# stm32103c8t6-10x10-v2.net
KiCad netlist of a schematic drawn in EAGLE
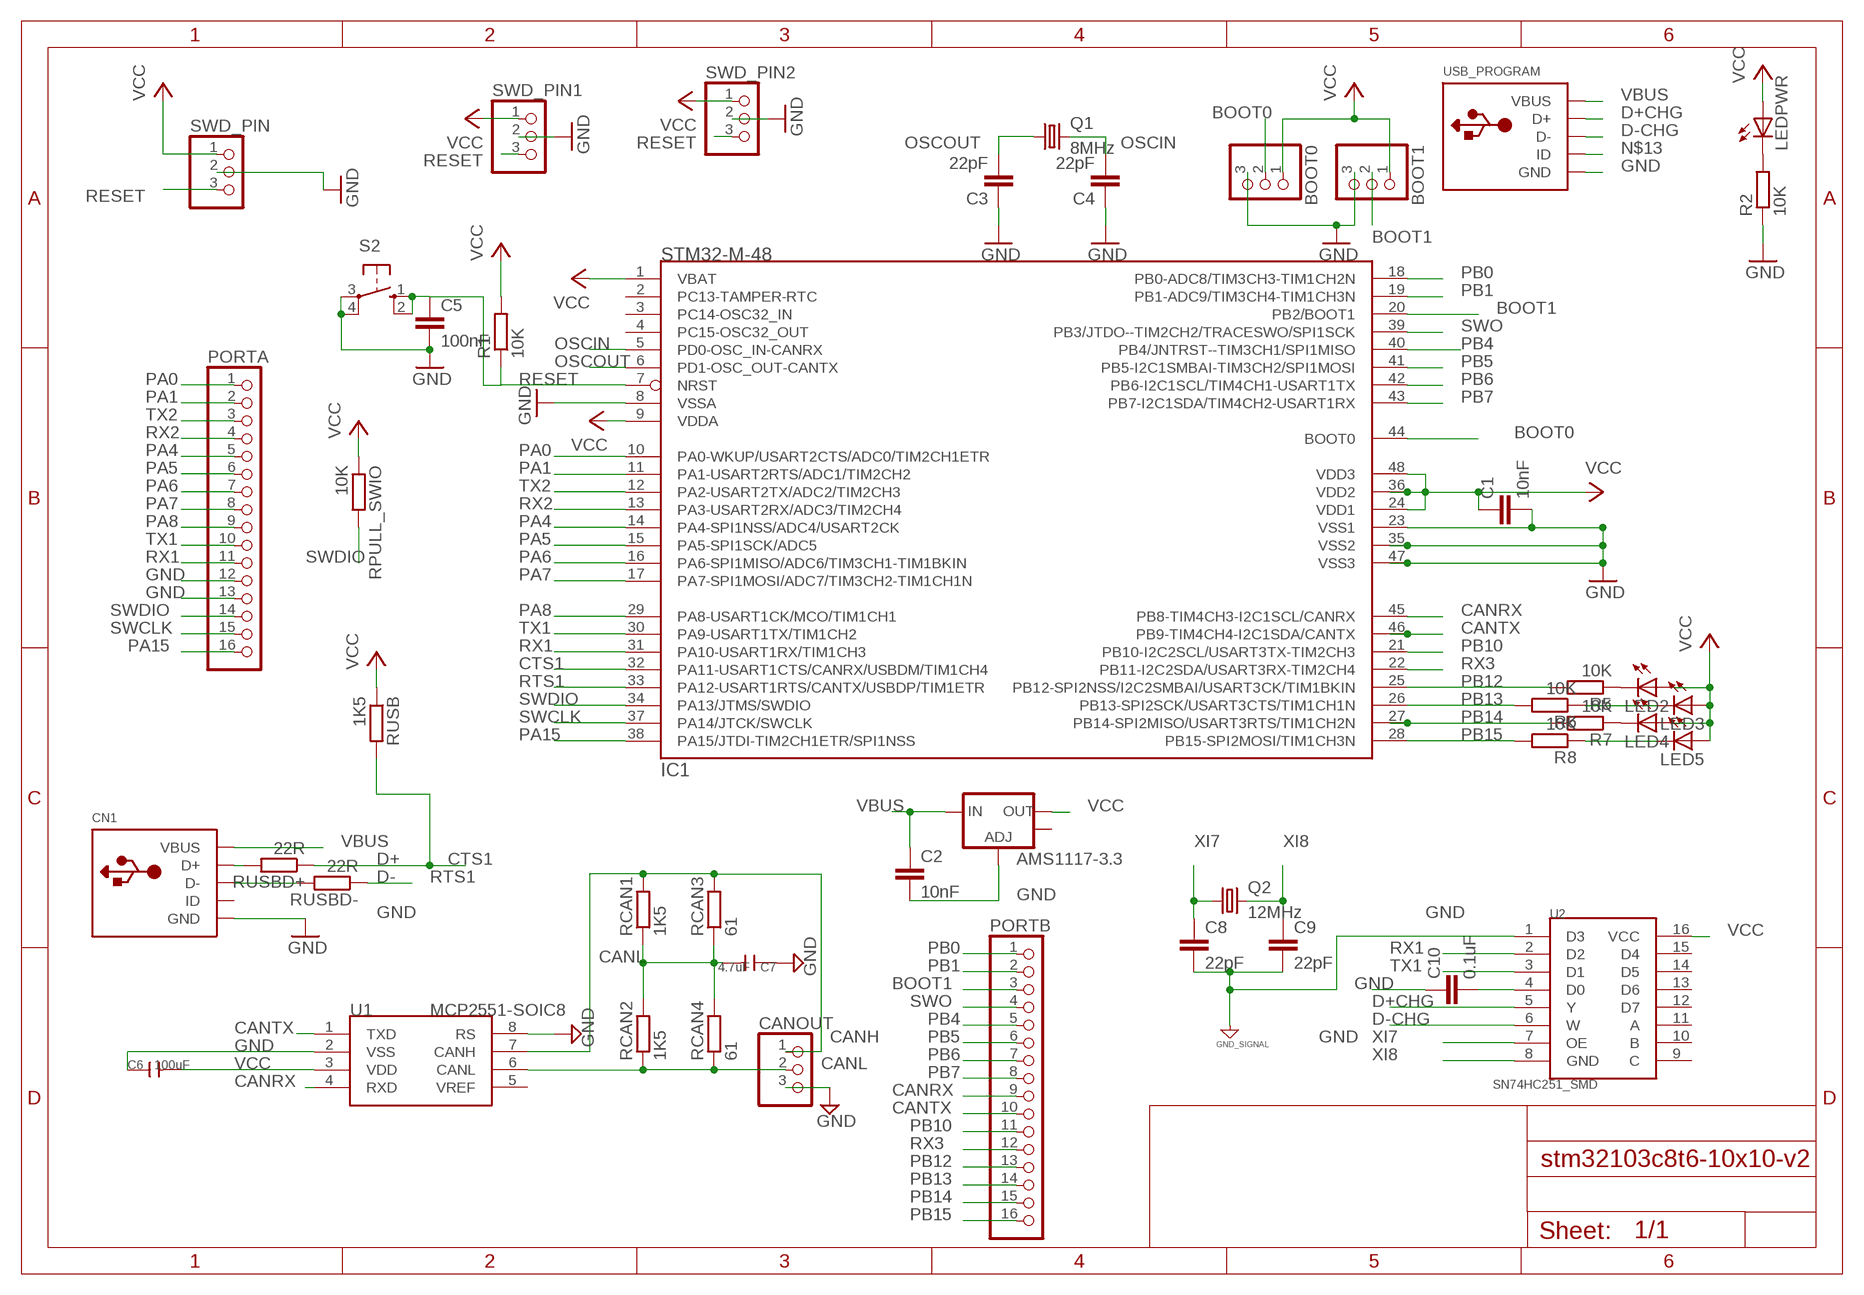
[diagram p0: schematic, sheet 1]

(export (version "E")
  (design (tool "Eeschema 10.0.6"))
  (components
    (comp (ref "AMS1117-3.3")
      (value "V_REG_LM1117SOT223")
      (footprint "eagle-import:SOT223")
      (libsource (lib "eagle-import") (part "V_REG_LM1117SOT223"))
    )
    (comp (ref "BOOT0")
      (value "PINHD-1X3")
      (footprint "eagle-import:1X03")
      (libsource (lib "eagle-import") (part "PINHD-1X3"))
    )
    (comp (ref "BOOT1")
      (value "PINHD-1X3")
      (footprint "eagle-import:1X03")
      (libsource (lib "eagle-import") (part "PINHD-1X3"))
    )
    (comp (ref "C1")
      (value "10nF")
      (footprint "eagle-import:C1210")
      (libsource (lib "eagle-import") (part "C-EUC1210"))
    )
    (comp (ref "C2")
      (value "10nF")
      (footprint "eagle-import:C1206")
      (libsource (lib "eagle-import") (part "C-EUC1206"))
    )
    (comp (ref "C3")
      (value "22pF")
      (footprint "eagle-import:C1210")
      (libsource (lib "eagle-import") (part "C-EUC1210"))
    )
    (comp (ref "C4")
      (value "22pF")
      (footprint "eagle-import:C1210")
      (libsource (lib "eagle-import") (part "C-EUC1210"))
    )
    (comp (ref "C5")
      (value "100nF")
      (footprint "eagle-import:C1206")
      (libsource (lib "eagle-import") (part "C-EUC1206"))
    )
    (comp (ref "C6")
      (value "100uF")
      (footprint "eagle-import:C1206")
      (libsource (lib "eagle-import") (part "C-1206"))
    )
    (comp (ref "C7")
      (value "4.7uF")
      (footprint "eagle-import:C1206")
      (libsource (lib "eagle-import") (part "C-1206"))
    )
    (comp (ref "C8")
      (value "22pF")
      (footprint "eagle-import:C1206")
      (libsource (lib "eagle-import") (part "C-EUC1206"))
    )
    (comp (ref "C9")
      (value "22pF")
      (footprint "eagle-import:C1206")
      (libsource (lib "eagle-import") (part "C-EUC1206"))
    )
    (comp (ref "C10")
      (value "0.1uF")
      (footprint "eagle-import:C1206")
      (libsource (lib "eagle-import") (part "C-EUC1206"))
    )
    (comp (ref "CANOUT")
      (value "PINHD-1X3")
      (footprint "eagle-import:1X03")
      (libsource (lib "eagle-import") (part "PINHD-1X3"))
    )
    (comp (ref "CN1")
      (value "USBTHM")
      (footprint "eagle-import:USB-MINIB-THM")
      (libsource (lib "eagle-import") (part "USBTHM"))
    )
    (comp (ref "IC1")
      (value "STM32-M-48")
      (footprint "eagle-import:LQFP48")
      (libsource (lib "eagle-import") (part "STM32-M-48"))
    )
    (comp (ref "LED2")
      (value "LEDSMT1206")
      (footprint "eagle-import:1206")
      (libsource (lib "eagle-import") (part "LEDSMT1206"))
    )
    (comp (ref "LED3")
      (value "LEDSMT1206")
      (footprint "eagle-import:1206")
      (libsource (lib "eagle-import") (part "LEDSMT1206"))
    )
    (comp (ref "LED4")
      (value "LEDSMT1206")
      (footprint "eagle-import:1206")
      (libsource (lib "eagle-import") (part "LEDSMT1206"))
    )
    (comp (ref "LED5")
      (value "LEDSMT1206")
      (footprint "eagle-import:1206")
      (libsource (lib "eagle-import") (part "LEDSMT1206"))
    )
    (comp (ref "LEDPWR")
      (value "LEDSMT1206")
      (footprint "eagle-import:1206")
      (libsource (lib "eagle-import") (part "LEDSMT1206"))
    )
    (comp (ref "PORTA")
      (value "PINHD-1X16")
      (footprint "eagle-import:1X16")
      (libsource (lib "eagle-import") (part "PINHD-1X16"))
    )
    (comp (ref "PORTB")
      (value "PINHD-1X16")
      (footprint "eagle-import:1X16")
      (libsource (lib "eagle-import") (part "PINHD-1X16"))
    )
    (comp (ref "Q1")
      (value "8MHz")
      (footprint "eagle-import:HC49_S")
      (libsource (lib "eagle-import") (part "CRYSTALHC49S"))
    )
    (comp (ref "Q2")
      (value "12MHz")
      (footprint "eagle-import:HC49_S")
      (libsource (lib "eagle-import") (part "CRYSTALHC49S"))
    )
    (comp (ref "R1")
      (value "10K")
      (footprint "eagle-import:R1206")
      (libsource (lib "eagle-import") (part "R-EU_R1206"))
    )
    (comp (ref "R2")
      (value "10K")
      (footprint "eagle-import:R1206")
      (libsource (lib "eagle-import") (part "R-EU_R1206"))
    )
    (comp (ref "R5")
      (value "10K")
      (footprint "eagle-import:R1206")
      (libsource (lib "eagle-import") (part "R-EU_R1206"))
    )
    (comp (ref "R6")
      (value "10K")
      (footprint "eagle-import:R1206")
      (libsource (lib "eagle-import") (part "R-EU_R1206"))
    )
    (comp (ref "R7")
      (value "10K")
      (footprint "eagle-import:R1206")
      (libsource (lib "eagle-import") (part "R-EU_R1206"))
    )
    (comp (ref "R8")
      (value "10K")
      (footprint "eagle-import:R1206")
      (libsource (lib "eagle-import") (part "R-EU_R1206"))
    )
    (comp (ref "RCAN1")
      (value "1K5")
      (footprint "eagle-import:R1206")
      (libsource (lib "eagle-import") (part "R-EU_R1206"))
    )
    (comp (ref "RCAN2")
      (value "1K5")
      (footprint "eagle-import:R1206")
      (libsource (lib "eagle-import") (part "R-EU_R1206"))
    )
    (comp (ref "RCAN3")
      (value "61")
      (footprint "eagle-import:R1206")
      (libsource (lib "eagle-import") (part "R-EU_R1206"))
    )
    (comp (ref "RCAN4")
      (value "61")
      (footprint "eagle-import:R1206")
      (libsource (lib "eagle-import") (part "R-EU_R1206"))
    )
    (comp (ref "RPULL_SWIO")
      (value "10K")
      (footprint "eagle-import:R1206")
      (libsource (lib "eagle-import") (part "R-EU_R1206"))
    )
    (comp (ref "RUSB")
      (value "1K5")
      (footprint "eagle-import:R1206")
      (libsource (lib "eagle-import") (part "R-EU_R1206"))
    )
    (comp (ref "RUSBD+")
      (value "22R")
      (footprint "eagle-import:R1206")
      (libsource (lib "eagle-import") (part "R-EU_R1206"))
    )
    (comp (ref "RUSBD-")
      (value "22R")
      (footprint "eagle-import:R1206")
      (libsource (lib "eagle-import") (part "R-EU_R1206"))
    )
    (comp (ref "S2")
      (value "10-XX")
      (footprint "eagle-import:B3F-10XX")
      (fields (field (name "MPN") "B3F-1000"))
      (libsource (lib "eagle-import") (part "10-XX"))
    )
    (comp (ref "SWD_PIN")
      (value "PINHD-1X3")
      (footprint "eagle-import:1X03")
      (libsource (lib "eagle-import") (part "PINHD-1X3"))
    )
    (comp (ref "SWD_PIN1")
      (value "PINHD-1X3")
      (footprint "eagle-import:1X03")
      (libsource (lib "eagle-import") (part "PINHD-1X3"))
    )
    (comp (ref "SWD_PIN2")
      (value "PINHD-1X3")
      (footprint "eagle-import:1X03")
      (libsource (lib "eagle-import") (part "PINHD-1X3"))
    )
    (comp (ref "U1")
      (value "MCP2551-SOIC8")
      (footprint "eagle-import:SOIC8-6.0")
      (libsource (lib "eagle-import") (part "MCP2551-SOIC8"))
    )
    (comp (ref "U2")
      (value "SN74HC251_SMD")
      (footprint "eagle-import:SO016")
      (libsource (lib "eagle-import") (part "SN74HC251_SMD"))
    )
    (comp (ref "USB_PROGRAM")
      (value "USBTHM")
      (footprint "eagle-import:USB-MINIB-THM")
      (libsource (lib "eagle-import") (part "USBTHM"))
    )
  )
  (nets
    (net (code "1") (name "/BOOT0") (class "Default")
      (node (ref "BOOT0") (pin "2") (pinfunction "2_2") (pintype "passive"))
      (node (ref "IC1") (pin "44") (pinfunction "BOOT0_44") (pintype "input"))
    )
    (net (code "2") (name "/BOOT1") (class "Default")
      (node (ref "BOOT1") (pin "2") (pinfunction "2_2") (pintype "passive"))
      (node (ref "IC1") (pin "20") (pinfunction "PB2/BOOT1_20") (pintype "bidirectional"))
      (node (ref "PORTB") (pin "3") (pinfunction "3_3") (pintype "passive"))
    )
    (net (code "3") (name "/CANH") (class "Default")
      (node (ref "CANOUT") (pin "1") (pinfunction "1_1") (pintype "passive"))
      (node (ref "RCAN1") (pin "2") (pinfunction "2_2") (pintype "passive"))
      (node (ref "RCAN3") (pin "2") (pinfunction "2_2") (pintype "passive"))
      (node (ref "U1") (pin "7") (pinfunction "CANH_7") (pintype "bidirectional"))
    )
    (net (code "4") (name "/CANL") (class "Default")
      (node (ref "CANOUT") (pin "2") (pinfunction "2_2") (pintype "passive"))
      (node (ref "RCAN2") (pin "1") (pinfunction "1_1") (pintype "passive"))
      (node (ref "RCAN4") (pin "1") (pinfunction "1_1") (pintype "passive"))
      (node (ref "U1") (pin "6") (pinfunction "CANL_6") (pintype "bidirectional"))
    )
    (net (code "5") (name "/CANRX") (class "Default")
      (node (ref "IC1") (pin "45") (pinfunction "PB8-TIM4CH3-I2C1SCL/CANRX_45") (pintype "bidirectional"))
      (node (ref "PORTB") (pin "9") (pinfunction "9_9") (pintype "passive"))
      (node (ref "U1") (pin "4") (pinfunction "RXD_4") (pintype "bidirectional"))
    )
    (net (code "6") (name "/CANTX") (class "Default")
      (node (ref "IC1") (pin "46") (pinfunction "PB9-TIM4CH4-I2C1SDA/CANTX_46") (pintype "bidirectional"))
      (node (ref "PORTB") (pin "10") (pinfunction "10_10") (pintype "passive"))
      (node (ref "U1") (pin "1") (pinfunction "TXD_1") (pintype "bidirectional"))
    )
    (net (code "7") (name "/CTS1") (class "Default")
      (node (ref "IC1") (pin "32") (pinfunction "PA11-USART1CTS/CANRX/USBDM/TIM1CH4_32") (pintype "bidirectional"))
      (node (ref "RUSB") (pin "2") (pinfunction "2_2") (pintype "passive"))
      (node (ref "RUSBD+") (pin "1") (pinfunction "1_1") (pintype "passive"))
    )
    (net (code "8") (name "/D+") (class "Default")
      (node (ref "CN1") (pin "D+") (pinfunction "D+_D+") (pintype "bidirectional"))
      (node (ref "RUSBD+") (pin "2") (pinfunction "2_2") (pintype "passive"))
    )
    (net (code "9") (name "/D+CHG") (class "Default")
      (node (ref "U2") (pin "5") (pinfunction "Y_5") (pintype "bidirectional"))
      (node (ref "USB_PROGRAM") (pin "D+") (pinfunction "D+_D+") (pintype "bidirectional"))
    )
    (net (code "10") (name "/D-") (class "Default")
      (node (ref "CN1") (pin "D-") (pinfunction "D-_D-") (pintype "bidirectional"))
      (node (ref "RUSBD-") (pin "2") (pinfunction "2_2") (pintype "passive"))
    )
    (net (code "11") (name "/D-CHG") (class "Default")
      (node (ref "U2") (pin "6") (pinfunction "W_6") (pintype "bidirectional"))
      (node (ref "USB_PROGRAM") (pin "D-") (pinfunction "D-_D-") (pintype "bidirectional"))
    )
    (net (code "12") (name "/N$13") (class "Default")
      (node (ref "USB_PROGRAM") (pin "ID") (pinfunction "ID_ID") (pintype "bidirectional"))
    )
    (net (code "13") (name "/OSCIN") (class "Default")
      (node (ref "C4") (pin "2") (pinfunction "2_2") (pintype "passive"))
      (node (ref "IC1") (pin "5") (pinfunction "PD0-OSC_IN-CANRX_5") (pintype "input"))
      (node (ref "Q1") (pin "2") (pinfunction "2_2") (pintype "passive"))
    )
    (net (code "14") (name "/OSCOUT") (class "Default")
      (node (ref "C3") (pin "2") (pinfunction "2_2") (pintype "passive"))
      (node (ref "IC1") (pin "6") (pinfunction "PD1-OSC_OUT-CANTX_6") (pintype "output"))
      (node (ref "Q1") (pin "1") (pinfunction "1_1") (pintype "passive"))
    )
    (net (code "15") (name "/PA0") (class "Default")
      (node (ref "IC1") (pin "10") (pinfunction "PA0-WKUP/USART2CTS/ADC0/TIM2CH1ETR_10") (pintype "bidirectional"))
      (node (ref "PORTA") (pin "1") (pinfunction "1_1") (pintype "passive"))
    )
    (net (code "16") (name "/PA1") (class "Default")
      (node (ref "IC1") (pin "11") (pinfunction "PA1-USART2RTS/ADC1/TIM2CH2_11") (pintype "bidirectional"))
      (node (ref "PORTA") (pin "2") (pinfunction "2_2") (pintype "passive"))
    )
    (net (code "17") (name "/PA4") (class "Default")
      (node (ref "IC1") (pin "14") (pinfunction "PA4-SPI1NSS/ADC4/USART2CK_14") (pintype "bidirectional"))
      (node (ref "PORTA") (pin "5") (pinfunction "5_5") (pintype "passive"))
    )
    (net (code "18") (name "/PA5") (class "Default")
      (node (ref "IC1") (pin "15") (pinfunction "PA5-SPI1SCK/ADC5_15") (pintype "bidirectional"))
      (node (ref "PORTA") (pin "6") (pinfunction "6_6") (pintype "passive"))
    )
    (net (code "19") (name "/PA6") (class "Default")
      (node (ref "IC1") (pin "16") (pinfunction "PA6-SPI1MISO/ADC6/TIM3CH1-TIM1BKIN_16") (pintype "bidirectional"))
      (node (ref "PORTA") (pin "7") (pinfunction "7_7") (pintype "passive"))
    )
    (net (code "20") (name "/PA7") (class "Default")
      (node (ref "IC1") (pin "17") (pinfunction "PA7-SPI1MOSI/ADC7/TIM3CH2-TIM1CH1N_17") (pintype "bidirectional"))
      (node (ref "PORTA") (pin "8") (pinfunction "8_8") (pintype "passive"))
    )
    (net (code "21") (name "/PA8") (class "Default")
      (node (ref "IC1") (pin "29") (pinfunction "PA8-USART1CK/MCO/TIM1CH1_29") (pintype "bidirectional"))
      (node (ref "PORTA") (pin "9") (pinfunction "9_9") (pintype "passive"))
    )
    (net (code "22") (name "/PA15") (class "Default")
      (node (ref "IC1") (pin "38") (pinfunction "PA15/JTDI-TIM2CH1ETR/SPI1NSS_38") (pintype "bidirectional"))
      (node (ref "PORTA") (pin "16") (pinfunction "16_16") (pintype "passive"))
    )
    (net (code "23") (name "/PB0") (class "Default")
      (node (ref "IC1") (pin "18") (pinfunction "PB0-ADC8/TIM3CH3-TIM1CH2N_18") (pintype "bidirectional"))
      (node (ref "PORTB") (pin "1") (pinfunction "1_1") (pintype "passive"))
    )
    (net (code "24") (name "/PB1") (class "Default")
      (node (ref "IC1") (pin "19") (pinfunction "PB1-ADC9/TIM3CH4-TIM1CH3N_19") (pintype "bidirectional"))
      (node (ref "PORTB") (pin "2") (pinfunction "2_2") (pintype "passive"))
    )
    (net (code "25") (name "/PB4") (class "Default")
      (node (ref "IC1") (pin "40") (pinfunction "PB4/JNTRST--TIM3CH1/SPI1MISO_40") (pintype "bidirectional"))
      (node (ref "PORTB") (pin "5") (pinfunction "5_5") (pintype "passive"))
    )
    (net (code "26") (name "/PB5") (class "Default")
      (node (ref "IC1") (pin "41") (pinfunction "PB5-I2C1SMBAI-TIM3CH2/SPI1MOSI_41") (pintype "bidirectional"))
      (node (ref "PORTB") (pin "6") (pinfunction "6_6") (pintype "passive"))
    )
    (net (code "27") (name "/PB6") (class "Default")
      (node (ref "IC1") (pin "42") (pinfunction "PB6-I2C1SCL/TIM4CH1-USART1TX_42") (pintype "bidirectional"))
      (node (ref "PORTB") (pin "7") (pinfunction "7_7") (pintype "passive"))
    )
    (net (code "28") (name "/PB7") (class "Default")
      (node (ref "IC1") (pin "43") (pinfunction "PB7-I2C1SDA/TIM4CH2-USART1RX_43") (pintype "bidirectional"))
      (node (ref "PORTB") (pin "8") (pinfunction "8_8") (pintype "passive"))
    )
    (net (code "29") (name "/PB10") (class "Default")
      (node (ref "IC1") (pin "21") (pinfunction "PB10-I2C2SCL/USART3TX-TIM2CH3_21") (pintype "bidirectional"))
      (node (ref "PORTB") (pin "11") (pinfunction "11_11") (pintype "passive"))
    )
    (net (code "30") (name "/PB12") (class "Default")
      (node (ref "IC1") (pin "25") (pinfunction "PB12-SPI2NSS/I2C2SMBAI/USART3CK/TIM1BKIN_25") (pintype "bidirectional"))
      (node (ref "PORTB") (pin "13") (pinfunction "13_13") (pintype "passive"))
      (node (ref "R5") (pin "2") (pinfunction "2_2") (pintype "passive"))
    )
    (net (code "31") (name "/PB13") (class "Default")
      (node (ref "IC1") (pin "26") (pinfunction "PB13-SPI2SCK/USART3CTS/TIM1CH1N_26") (pintype "bidirectional"))
      (node (ref "PORTB") (pin "14") (pinfunction "14_14") (pintype "passive"))
      (node (ref "R6") (pin "2") (pinfunction "2_2") (pintype "passive"))
    )
    (net (code "32") (name "/PB14") (class "Default")
      (node (ref "IC1") (pin "27") (pinfunction "PB14-SPI2MISO/USART3RTS/TIM1CH2N_27") (pintype "bidirectional"))
      (node (ref "PORTB") (pin "15") (pinfunction "15_15") (pintype "passive"))
      (node (ref "R7") (pin "2") (pinfunction "2_2") (pintype "passive"))
    )
    (net (code "33") (name "/PB15") (class "Default")
      (node (ref "IC1") (pin "28") (pinfunction "PB15-SPI2MOSI/TIM1CH3N_28") (pintype "bidirectional"))
      (node (ref "PORTB") (pin "16") (pinfunction "16_16") (pintype "passive"))
      (node (ref "R8") (pin "2") (pinfunction "2_2") (pintype "passive"))
    )
    (net (code "34") (name "/RESET") (class "Default")
      (node (ref "C5") (pin "1") (pinfunction "1_1") (pintype "passive"))
      (node (ref "IC1") (pin "7") (pinfunction "NRST_7") (pintype "bidirectional"))
      (node (ref "R1") (pin "1") (pinfunction "1_1") (pintype "passive"))
      (node (ref "S2") (pin "1") (pinfunction "S_1") (pintype "passive"))
      (node (ref "S2") (pin "2") (pinfunction "S1_2") (pintype "passive"))
      (node (ref "SWD_PIN") (pin "3") (pinfunction "3_3") (pintype "passive"))
      (node (ref "SWD_PIN1") (pin "3") (pinfunction "3_3") (pintype "passive"))
      (node (ref "SWD_PIN2") (pin "3") (pinfunction "3_3") (pintype "passive"))
    )
    (net (code "35") (name "/RTS1") (class "Default")
      (node (ref "IC1") (pin "33") (pinfunction "PA12-USART1RTS/CANTX/USBDP/TIM1ETR_33") (pintype "bidirectional"))
      (node (ref "RUSBD-") (pin "1") (pinfunction "1_1") (pintype "passive"))
    )
    (net (code "36") (name "/RX1") (class "Default")
      (node (ref "IC1") (pin "31") (pinfunction "PA10-USART1RX/TIM1CH3_31") (pintype "bidirectional"))
      (node (ref "PORTA") (pin "11") (pinfunction "11_11") (pintype "passive"))
      (node (ref "U2") (pin "2") (pinfunction "D2_2") (pintype "bidirectional"))
    )
    (net (code "37") (name "/RX2") (class "Default")
      (node (ref "IC1") (pin "13") (pinfunction "PA3-USART2RX/ADC3/TIM2CH4_13") (pintype "bidirectional"))
      (node (ref "PORTA") (pin "4") (pinfunction "4_4") (pintype "passive"))
    )
    (net (code "38") (name "/RX3") (class "Default")
      (node (ref "IC1") (pin "22") (pinfunction "PB11-I2C2SDA/USART3RX-TIM2CH4_22") (pintype "bidirectional"))
      (node (ref "PORTB") (pin "12") (pinfunction "12_12") (pintype "passive"))
    )
    (net (code "39") (name "/SWCLK") (class "Default")
      (node (ref "IC1") (pin "37") (pinfunction "PA14/JTCK/SWCLK_37") (pintype "bidirectional"))
      (node (ref "PORTA") (pin "15") (pinfunction "15_15") (pintype "passive"))
    )
    (net (code "40") (name "/SWDIO") (class "Default")
      (node (ref "IC1") (pin "34") (pinfunction "PA13/JTMS/SWDIO_34") (pintype "bidirectional"))
      (node (ref "PORTA") (pin "14") (pinfunction "14_14") (pintype "passive"))
      (node (ref "RPULL_SWIO") (pin "2") (pinfunction "2_2") (pintype "passive"))
    )
    (net (code "41") (name "/SWO") (class "Default")
      (node (ref "IC1") (pin "39") (pinfunction "PB3/JTDO--TIM2CH2/TRACESWO/SPI1SCK_39") (pintype "bidirectional"))
      (node (ref "PORTB") (pin "4") (pinfunction "4_4") (pintype "passive"))
    )
    (net (code "42") (name "/TX1") (class "Default")
      (node (ref "IC1") (pin "30") (pinfunction "PA9-USART1TX/TIM1CH2_30") (pintype "bidirectional"))
      (node (ref "PORTA") (pin "10") (pinfunction "10_10") (pintype "passive"))
      (node (ref "U2") (pin "3") (pinfunction "D1_3") (pintype "bidirectional"))
    )
    (net (code "43") (name "/TX2") (class "Default")
      (node (ref "IC1") (pin "12") (pinfunction "PA2-USART2TX/ADC2/TIM2CH3_12") (pintype "bidirectional"))
      (node (ref "PORTA") (pin "3") (pinfunction "3_3") (pintype "passive"))
    )
    (net (code "44") (name "/VBUS") (class "Default")
      (node (ref "AMS1117-3.3") (pin "3") (pinfunction "IN_3") (pintype "input"))
      (node (ref "C2") (pin "1") (pinfunction "1_1") (pintype "passive"))
      (node (ref "CN1") (pin "VBUS") (pinfunction "VBUS_VBUS") (pintype "power_in"))
      (node (ref "USB_PROGRAM") (pin "VBUS") (pinfunction "VBUS_VBUS") (pintype "power_in"))
    )
    (net (code "45") (name "/XI7") (class "Default")
      (node (ref "C8") (pin "1") (pinfunction "1_1") (pintype "passive"))
      (node (ref "Q2") (pin "1") (pinfunction "1_1") (pintype "passive"))
      (node (ref "U2") (pin "7") (pinfunction "OE_7") (pintype "bidirectional"))
    )
    (net (code "46") (name "/XI8") (class "Default")
      (node (ref "C9") (pin "1") (pinfunction "1_1") (pintype "passive"))
      (node (ref "Q2") (pin "2") (pinfunction "2_2") (pintype "passive"))
      (node (ref "U2") (pin "8") (pinfunction "GND_8") (pintype "bidirectional"))
    )
    (net (code "47") (name "GND") (class "Default")
      (node (ref "AMS1117-3.3") (pin "1") (pinfunction "ADJ_1") (pintype "input"))
      (node (ref "BOOT0") (pin "3") (pinfunction "3_3") (pintype "passive"))
      (node (ref "BOOT1") (pin "3") (pinfunction "3_3") (pintype "passive"))
      (node (ref "C1") (pin "2") (pinfunction "2_2") (pintype "passive"))
      (node (ref "C10") (pin "1") (pinfunction "1_1") (pintype "passive"))
      (node (ref "C2") (pin "2") (pinfunction "2_2") (pintype "passive"))
      (node (ref "C3") (pin "1") (pinfunction "1_1") (pintype "passive"))
      (node (ref "C4") (pin "1") (pinfunction "1_1") (pintype "passive"))
      (node (ref "C5") (pin "2") (pinfunction "2_2") (pintype "passive"))
      (node (ref "C6") (pin "1") (pinfunction "1_1") (pintype "passive"))
      (node (ref "C7") (pin "1") (pinfunction "1_1") (pintype "passive"))
      (node (ref "C8") (pin "2") (pinfunction "2_2") (pintype "passive"))
      (node (ref "C9") (pin "2") (pinfunction "2_2") (pintype "passive"))
      (node (ref "CANOUT") (pin "3") (pinfunction "3_3") (pintype "passive"))
      (node (ref "CN1") (pin "GND") (pinfunction "GND_GND") (pintype "power_in"))
      (node (ref "IC1") (pin "23") (pinfunction "VSS1_23") (pintype "power_in"))
      (node (ref "IC1") (pin "35") (pinfunction "VSS2_35") (pintype "power_in"))
      (node (ref "IC1") (pin "47") (pinfunction "VSS3_47") (pintype "power_in"))
      (node (ref "IC1") (pin "8") (pinfunction "VSSA_8") (pintype "power_in"))
      (node (ref "PORTA") (pin "12") (pinfunction "12_12") (pintype "passive"))
      (node (ref "PORTA") (pin "13") (pinfunction "13_13") (pintype "passive"))
      (node (ref "R2") (pin "1") (pinfunction "1_1") (pintype "passive"))
      (node (ref "S2") (pin "3") (pinfunction "P_3") (pintype "passive"))
      (node (ref "S2") (pin "4") (pinfunction "P1_4") (pintype "passive"))
      (node (ref "SWD_PIN") (pin "2") (pinfunction "2_2") (pintype "passive"))
      (node (ref "SWD_PIN1") (pin "2") (pinfunction "2_2") (pintype "passive"))
      (node (ref "SWD_PIN2") (pin "2") (pinfunction "2_2") (pintype "passive"))
      (node (ref "U1") (pin "2") (pinfunction "VSS_2") (pintype "bidirectional"))
      (node (ref "U1") (pin "8") (pinfunction "RS_8") (pintype "bidirectional"))
      (node (ref "U2") (pin "1") (pinfunction "D3_1") (pintype "bidirectional"))
      (node (ref "USB_PROGRAM") (pin "GND") (pinfunction "GND_GND") (pintype "power_in"))
    )
    (net (code "48") (name "Net-(C7-Pad2)") (class "Default")
      (node (ref "C7") (pin "2") (pinfunction "2_2") (pintype "passive"))
      (node (ref "RCAN1") (pin "1") (pinfunction "1_1") (pintype "passive"))
      (node (ref "RCAN2") (pin "2") (pinfunction "2_2") (pintype "passive"))
      (node (ref "RCAN3") (pin "1") (pinfunction "1_1") (pintype "passive"))
      (node (ref "RCAN4") (pin "2") (pinfunction "2_2") (pintype "passive"))
    )
    (net (code "49") (name "Net-(LED2-PadC)") (class "Default")
      (node (ref "LED2") (pin "C") (pinfunction "C_C") (pintype "passive"))
      (node (ref "R5") (pin "1") (pinfunction "1_1") (pintype "passive"))
    )
    (net (code "50") (name "Net-(LED3-PadC)") (class "Default")
      (node (ref "LED3") (pin "C") (pinfunction "C_C") (pintype "passive"))
      (node (ref "R6") (pin "1") (pinfunction "1_1") (pintype "passive"))
    )
    (net (code "51") (name "Net-(LED4-PadC)") (class "Default")
      (node (ref "LED4") (pin "C") (pinfunction "C_C") (pintype "passive"))
      (node (ref "R7") (pin "1") (pinfunction "1_1") (pintype "passive"))
    )
    (net (code "52") (name "Net-(LED5-PadC)") (class "Default")
      (node (ref "LED5") (pin "C") (pinfunction "C_C") (pintype "passive"))
      (node (ref "R8") (pin "1") (pinfunction "1_1") (pintype "passive"))
    )
    (net (code "53") (name "Net-(LEDPWR-PadC)") (class "Default")
      (node (ref "LEDPWR") (pin "C") (pinfunction "C_C") (pintype "passive"))
      (node (ref "R2") (pin "2") (pinfunction "2_2") (pintype "passive"))
    )
    (net (code "54") (name "Net-(U2-D0)") (class "Default")
      (node (ref "C10") (pin "2") (pinfunction "2_2") (pintype "passive"))
      (node (ref "U2") (pin "4") (pinfunction "D0_4") (pintype "bidirectional"))
    )
    (net (code "55") (name "VCC") (class "Default")
      (node (ref "AMS1117-3.3") (pin "2") (pinfunction "OUT_2") (pintype "output"))
      (node (ref "BOOT0") (pin "1") (pinfunction "1_1") (pintype "passive"))
      (node (ref "BOOT1") (pin "1") (pinfunction "1_1") (pintype "passive"))
      (node (ref "C1") (pin "1") (pinfunction "1_1") (pintype "passive"))
      (node (ref "C6") (pin "2") (pinfunction "2_2") (pintype "passive"))
      (node (ref "IC1") (pin "1") (pinfunction "VBAT_1") (pintype "power_in"))
      (node (ref "IC1") (pin "24") (pinfunction "VDD1_24") (pintype "power_in"))
      (node (ref "IC1") (pin "36") (pinfunction "VDD2_36") (pintype "power_in"))
      (node (ref "IC1") (pin "48") (pinfunction "VDD3_48") (pintype "power_in"))
      (node (ref "IC1") (pin "9") (pinfunction "VDDA_9") (pintype "power_in"))
      (node (ref "LED2") (pin "A") (pinfunction "A_A") (pintype "passive"))
      (node (ref "LED3") (pin "A") (pinfunction "A_A") (pintype "passive"))
      (node (ref "LED4") (pin "A") (pinfunction "A_A") (pintype "passive"))
      (node (ref "LED5") (pin "A") (pinfunction "A_A") (pintype "passive"))
      (node (ref "LEDPWR") (pin "A") (pinfunction "A_A") (pintype "passive"))
      (node (ref "R1") (pin "2") (pinfunction "2_2") (pintype "passive"))
      (node (ref "RPULL_SWIO") (pin "1") (pinfunction "1_1") (pintype "passive"))
      (node (ref "RUSB") (pin "1") (pinfunction "1_1") (pintype "passive"))
      (node (ref "SWD_PIN") (pin "1") (pinfunction "1_1") (pintype "passive"))
      (node (ref "SWD_PIN1") (pin "1") (pinfunction "1_1") (pintype "passive"))
      (node (ref "SWD_PIN2") (pin "1") (pinfunction "1_1") (pintype "passive"))
      (node (ref "U1") (pin "3") (pinfunction "VDD_3") (pintype "bidirectional"))
      (node (ref "U2") (pin "16") (pinfunction "VCC_16") (pintype "bidirectional"))
    )
    (net (code "56") (name "unconnected-(AMS1117-3.3-OUT-Pad4)") (class "Default")
      (node (ref "AMS1117-3.3") (pin "4") (pinfunction "OUT_4") (pintype "output"))
    )
    (net (code "57") (name "unconnected-(CN1-PadID)") (class "Default")
      (node (ref "CN1") (pin "ID") (pinfunction "ID_ID") (pintype "bidirectional"))
    )
    (net (code "58") (name "unconnected-(IC1-PC13-TAMPER-RTC-Pad2)") (class "Default")
      (node (ref "IC1") (pin "2") (pinfunction "PC13-TAMPER-RTC_2") (pintype "bidirectional"))
    )
    (net (code "59") (name "unconnected-(IC1-PC14-OSC32_IN-Pad3)") (class "Default")
      (node (ref "IC1") (pin "3") (pinfunction "PC14-OSC32_IN_3") (pintype "bidirectional"))
    )
    (net (code "60") (name "unconnected-(IC1-PC15-OSC32_OUT-Pad4)") (class "Default")
      (node (ref "IC1") (pin "4") (pinfunction "PC15-OSC32_OUT_4") (pintype "bidirectional"))
    )
    (net (code "61") (name "unconnected-(U1-VREF-Pad5)") (class "Default")
      (node (ref "U1") (pin "5") (pinfunction "VREF_5") (pintype "bidirectional"))
    )
    (net (code "62") (name "unconnected-(U2-A-Pad11)") (class "Default")
      (node (ref "U2") (pin "11") (pinfunction "A_11") (pintype "bidirectional"))
    )
    (net (code "63") (name "unconnected-(U2-B-Pad10)") (class "Default")
      (node (ref "U2") (pin "10") (pinfunction "B_10") (pintype "bidirectional"))
    )
    (net (code "64") (name "unconnected-(U2-C-Pad9)") (class "Default")
      (node (ref "U2") (pin "9") (pinfunction "C_9") (pintype "bidirectional"))
    )
    (net (code "65") (name "unconnected-(U2-D4-Pad15)") (class "Default")
      (node (ref "U2") (pin "15") (pinfunction "D4_15") (pintype "bidirectional"))
    )
    (net (code "66") (name "unconnected-(U2-D5-Pad14)") (class "Default")
      (node (ref "U2") (pin "14") (pinfunction "D5_14") (pintype "bidirectional"))
    )
    (net (code "67") (name "unconnected-(U2-D6-Pad13)") (class "Default")
      (node (ref "U2") (pin "13") (pinfunction "D6_13") (pintype "bidirectional"))
    )
    (net (code "68") (name "unconnected-(U2-D7-Pad12)") (class "Default")
      (node (ref "U2") (pin "12") (pinfunction "D7_12") (pintype "bidirectional"))
    )
  )
)
